# BATT_DCDC_TEST_BED.net
KiCad netlist of a schematic drawn in EAGLE
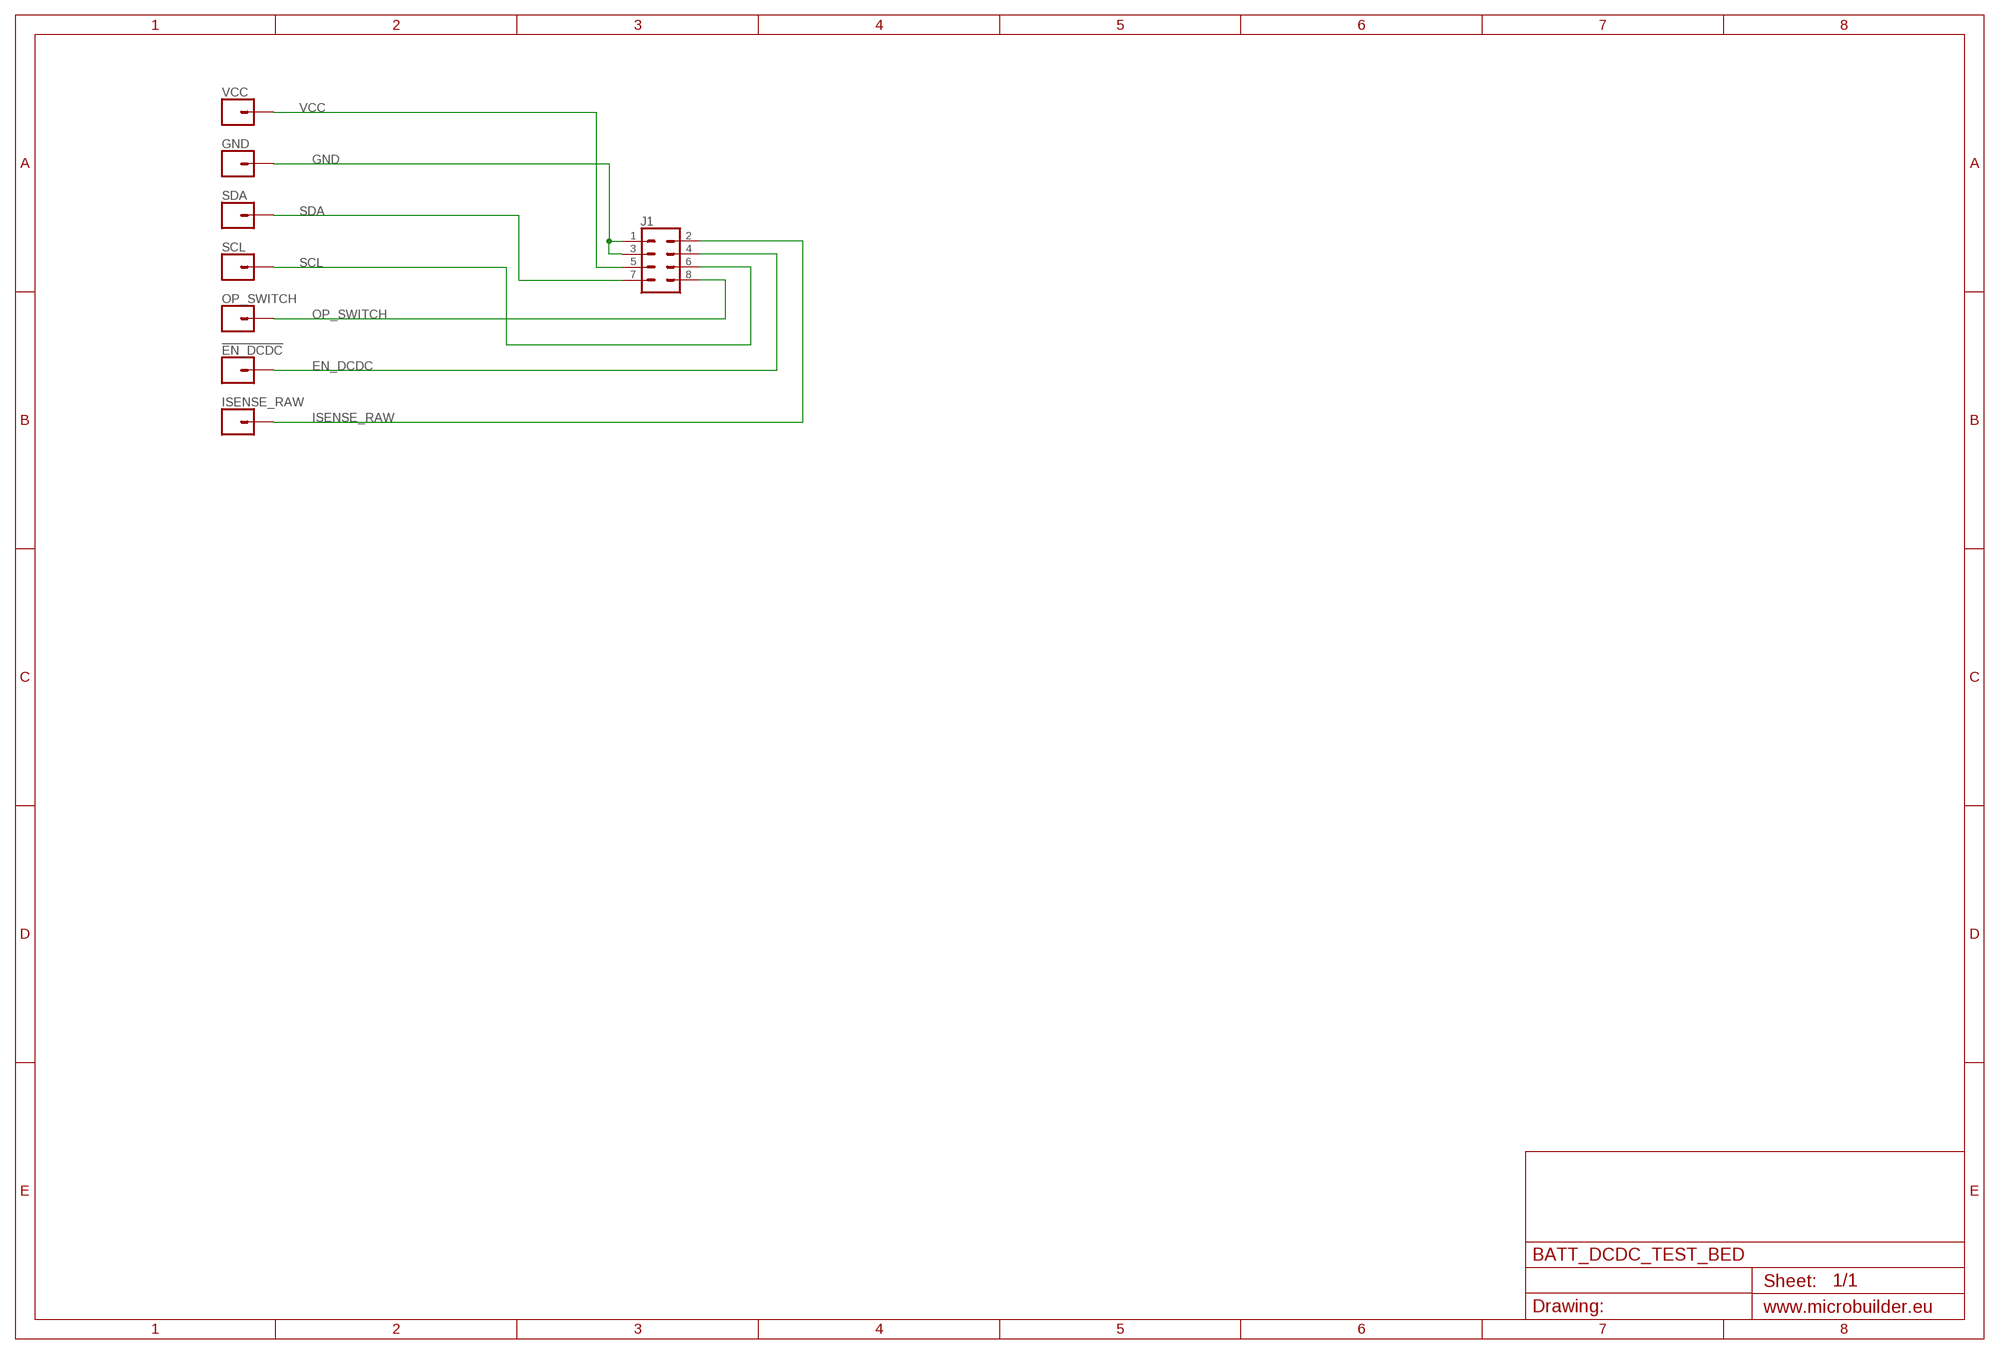
[diagram p0: schematic, sheet 1]

(export (version "E")
  (design (tool "Eeschema 10.0.6"))
  (components
    (comp (ref "!EN_DCDC!")
      (value "CONN_01POGOPIN_HOLE_LARGE")
      (footprint "eagle-import:1X01_POGOPIN_HOLE_0.061_DIA")
      (libsource (lib "eagle-import") (part "CONN_01POGOPIN_HOLE_LARGE"))
    )
    (comp (ref "GND")
      (value "CONN_01POGOPIN_HOLE_LARGE")
      (footprint "eagle-import:1X01_POGOPIN_HOLE_0.061_DIA")
      (libsource (lib "eagle-import") (part "CONN_01POGOPIN_HOLE_LARGE"))
    )
    (comp (ref "ISENSE_RAW")
      (value "CONN_01POGOPIN_HOLE_LARGE")
      (footprint "eagle-import:1X01_POGOPIN_HOLE_0.061_DIA")
      (libsource (lib "eagle-import") (part "CONN_01POGOPIN_HOLE_LARGE"))
    )
    (comp (ref "J1")
      (value "CONN_04X2")
      (footprint "eagle-import:2X4")
      (libsource (lib "eagle-import") (part "CONN_04X2"))
    )
    (comp (ref "OP_SWITCH")
      (value "CONN_01POGOPIN_HOLE_LARGE")
      (footprint "eagle-import:1X01_POGOPIN_HOLE_0.061_DIA")
      (libsource (lib "eagle-import") (part "CONN_01POGOPIN_HOLE_LARGE"))
    )
    (comp (ref "SCL")
      (value "CONN_01POGOPIN_HOLE_LARGE")
      (footprint "eagle-import:1X01_POGOPIN_HOLE_0.061_DIA")
      (libsource (lib "eagle-import") (part "CONN_01POGOPIN_HOLE_LARGE"))
    )
    (comp (ref "SDA")
      (value "CONN_01POGOPIN_HOLE_LARGE")
      (footprint "eagle-import:1X01_POGOPIN_HOLE_0.061_DIA")
      (libsource (lib "eagle-import") (part "CONN_01POGOPIN_HOLE_LARGE"))
    )
    (comp (ref "VCC")
      (value "CONN_01POGOPIN_HOLE_LARGE")
      (footprint "eagle-import:1X01_POGOPIN_HOLE_0.061_DIA")
      (libsource (lib "eagle-import") (part "CONN_01POGOPIN_HOLE_LARGE"))
    )
  )
  (nets
    (net (code "1") (name "/EN_DCDC") (class "Default")
      (node (ref "!EN_DCDC!") (pin "2") (pinfunction "1_2") (pintype "passive"))
      (node (ref "J1") (pin "4") (pinfunction "4_4") (pintype "passive"))
    )
    (net (code "2") (name "/GND") (class "Default")
      (node (ref "GND") (pin "2") (pinfunction "1_2") (pintype "passive"))
      (node (ref "J1") (pin "1") (pinfunction "1_1") (pintype "passive"))
      (node (ref "J1") (pin "3") (pinfunction "3_3") (pintype "passive"))
    )
    (net (code "3") (name "/ISENSE_RAW") (class "Default")
      (node (ref "ISENSE_RAW") (pin "2") (pinfunction "1_2") (pintype "passive"))
      (node (ref "J1") (pin "2") (pinfunction "2_2") (pintype "passive"))
    )
    (net (code "4") (name "/OP_SWITCH") (class "Default")
      (node (ref "J1") (pin "8") (pinfunction "8_8") (pintype "passive"))
      (node (ref "OP_SWITCH") (pin "2") (pinfunction "1_2") (pintype "passive"))
    )
    (net (code "5") (name "/SCL") (class "Default")
      (node (ref "J1") (pin "6") (pinfunction "6_6") (pintype "passive"))
      (node (ref "SCL") (pin "2") (pinfunction "1_2") (pintype "passive"))
    )
    (net (code "6") (name "/SDA") (class "Default")
      (node (ref "J1") (pin "7") (pinfunction "7_7") (pintype "passive"))
      (node (ref "SDA") (pin "2") (pinfunction "1_2") (pintype "passive"))
    )
    (net (code "7") (name "/VCC") (class "Default")
      (node (ref "J1") (pin "5") (pinfunction "5_5") (pintype "passive"))
      (node (ref "VCC") (pin "2") (pinfunction "1_2") (pintype "passive"))
    )
  )
)
